# Power_Circuit.net
KiCad netlist of a schematic drawn in Altium Designer
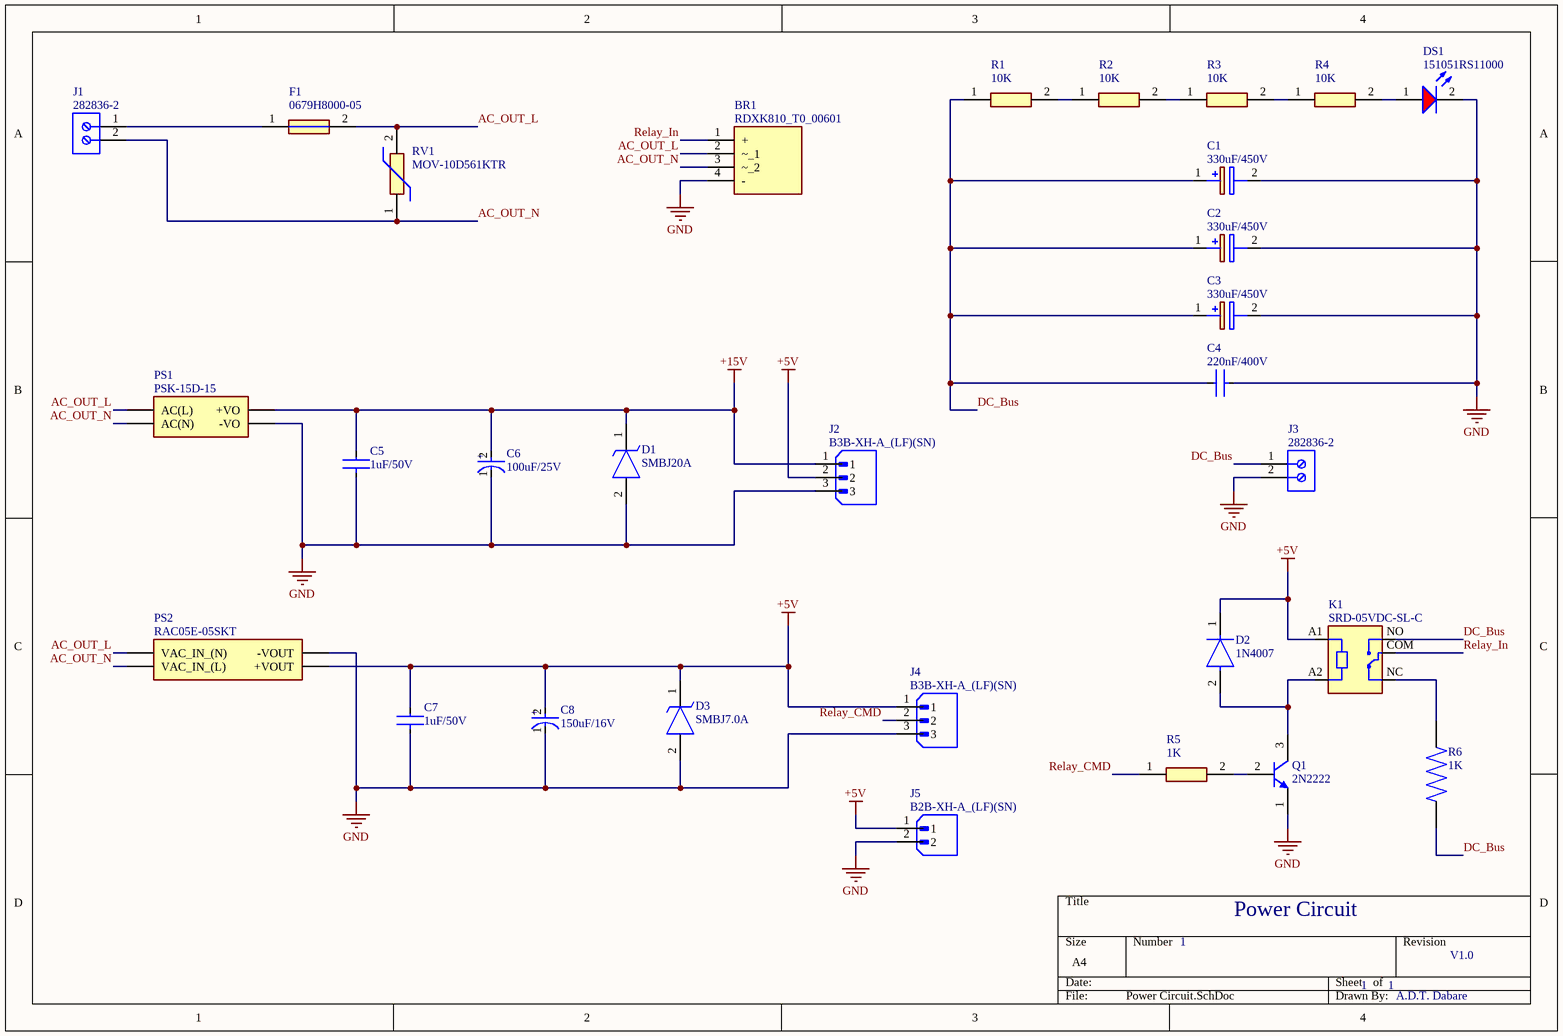
[diagram p0: Power Circuit.SchDoc]

(export (version "E")
  (design (tool "Eeschema 10.0.6"))
  (components
    (comp (ref "BR1")
      (value "RDXK810_T0_00601")
      (footprint "SamacSys:RDXK810_T0_00601")
      (description "Bridge Rectifier")
      (fields (field (name "MOUSER PART NUMBER") "241-RDXK810_T0_00601"))
      (libsource (lib "*") (part "RDXK810_T0_00601"))
    )
    (comp (ref "C1")
      (value "330uF/450V")
      (footprint "SamacSys:CAPPRD1000W190D3050H3200")
      (description "Capacitor Polarised")
      (fields
        (field (name "MANUFACTURER_PART_NUMBER") "B43647B5337M057")
        (field (name "MOUSER PART NUMBER") "871-B43647B5337M057")
      )
      (libsource (lib "*") (part "B43647B5337M057"))
    )
    (comp (ref "C2")
      (value "330uF/450V")
      (footprint "SamacSys:CAPPRD1000W190D3050H3200")
      (description "Capacitor Polarised")
      (fields
        (field (name "MANUFACTURER_PART_NUMBER") "B43647B5337M057")
        (field (name "MOUSER PART NUMBER") "871-B43647B5337M057")
      )
      (libsource (lib "*") (part "B43647B5337M057"))
    )
    (comp (ref "C3")
      (value "330uF/450V")
      (footprint "SamacSys:CAPPRD1000W190D3050H3200")
      (description "Capacitor Polarised")
      (fields
        (field (name "MANUFACTURER_PART_NUMBER") "B43647B5337M057")
        (field (name "MOUSER PART NUMBER") "871-B43647B5337M057")
      )
      (libsource (lib "*") (part "B43647B5337M057"))
    )
    (comp (ref "C4")
      (value "220nF/400V")
      (footprint "FP-CK06BX105K-MFG")
      (description "CAP CER 1UF 50V BX RADIAL")
      (fields (field (name "TOLERANCE") "10%"))
      (libsource (lib "Altium Content Vault") (part "b4654b650e69147ec39a6b967a45e02"))
    )
    (comp (ref "C5")
      (value "1uF/50V")
      (footprint "FP-CK06BX105K-MFG")
      (description "CAP CER 1UF 50V BX RADIAL")
      (fields (field (name "TOLERANCE") "10%"))
      (libsource (lib "Altium Content Vault") (part "b4654b650e69147ec39a6b967a45e02"))
    )
    (comp (ref "C6")
      (value "100uF/25V")
      (footprint "FP-RAD-TH-D_6_3_0_5-L_11-MFG")
      (description "Aluminum Electrolytic Capacitors (Radial Lead Type) AEC-Q200 Qualified 100uF ±20% 25V")
      (fields (field (name "TOLERANCE") "20%"))
      (libsource (lib "Altium Content Vault") (part "203bc49f2ac43e59fd269a8c329ed05"))
    )
    (comp (ref "C7")
      (value "1uF/50V")
      (footprint "FP-CK06BX105K-MFG")
      (description "CAP CER 1UF 50V BX RADIAL")
      (fields (field (name "TOLERANCE") "10%"))
      (libsource (lib "Altium Content Vault") (part "b4654b650e69147ec39a6b967a45e02"))
    )
    (comp (ref "C8")
      (value "150uF/16V")
      (footprint "FP-RAD-TH-D_6_3_0_5-L_11-MFG")
      (description "Aluminum Electrolytic Capacitors (Radial Lead Type) AEC-Q200 Qualified 100uF ±20% 25V")
      (fields (field (name "TOLERANCE") "20%"))
      (libsource (lib "Altium Content Vault") (part "203bc49f2ac43e59fd269a8c329ed05"))
    )
    (comp (ref "D1")
      (value "SMBJ20A")
      (footprint "SamacSys:DIOM5436X244N")
      (description "TVS Diode (Uni-directional)")
      (fields (field (name "MOUSER PART NUMBER") "652-SMBJ20A"))
      (libsource (lib "*") (part "SMBJ20A"))
    )
    (comp (ref "D2")
      (value "1N4007")
      (footprint "FP-1N4007-MFG")
      (description "Rectifier diode 1000 V 1 A DO-41, ,")
      (fields
        (field (name "MANUFACTURER") "Diotec")
        (field (name "OCTOPART") "https://octopart.com/1n4007-diotec-4040411")
      )
      (libsource (lib "Altium Content Vault") (part "d7152d700b627762746794eb795d46e"))
    )
    (comp (ref "D3")
      (value "SMBJ7.0A")
      (footprint "SamacSys:DIOM5443X244N")
      (description "TVS Diode (Uni-directional)")
      (fields (field (name "MOUSER PART NUMBER") "652-SMBJ7.0A"))
      (libsource (lib "*") (part "SMBJ7.0A"))
    )
    (comp (ref "DS1")
      (value "151051RS11000")
      (footprint "WL-TMRC_D5.9H8.7")
      (libsource (lib "Altium Content Vault") (part "LED_Red_1A-2K"))
    )
    (comp (ref "F1")
      (value "0679H8000-05")
      (footprint "SamacSys:FUSC6125X279N")
      (description "Fuse")
      (libsource (lib "*") (part "0679H8000-05"))
    )
    (comp (ref "J1")
      (value "282836-2")
      (footprint "TECO-282836-2_V")
      (description "Female Header, Pitch 5 mm, 1 x 2 Position, Height 10 mm, Tail Length 3.5 mm, Rohs, Bulk")
      (fields (field (name "VOLTAGE") "300V") (field (name "MANUFACTURER") "TE Connectivity"))
      (libsource (lib "Altium Content Vault") (part "CN-1P-F-TB2"))
    )
    (comp (ref "J2")
      (value "B3B-XH-A_(LF)(SN)")
      (footprint "JST_B3B-XH-A (LF)(SN)")
      (description "Connector Header Through Hole 3 position 0.098 (2.50mm)")
      (fields (field (name "MF") "JST Sales America Inc.") (field (name "MP") "B3B-XH-A (LF)(SN)"))
      (libsource (lib "B3B-XH-A__LF__SN_") (part "B3B-XH-A_(LF)(SN)"))
    )
    (comp (ref "J3")
      (value "282836-2")
      (footprint "TECO-282836-2_V")
      (description "Female Header, Pitch 5 mm, 1 x 2 Position, Height 10 mm, Tail Length 3.5 mm, Rohs, Bulk")
      (fields (field (name "VOLTAGE") "300V") (field (name "MANUFACTURER") "TE Connectivity"))
      (libsource (lib "Altium Content Vault") (part "CN-1P-F-TB2"))
    )
    (comp (ref "J4")
      (value "B3B-XH-A_(LF)(SN)")
      (footprint "JST_B3B-XH-A (LF)(SN)")
      (description "Connector Header Through Hole 3 position 0.098 (2.50mm)")
      (fields (field (name "MF") "JST Sales America Inc.") (field (name "MP") "B3B-XH-A (LF)(SN)"))
      (libsource (lib "B3B-XH-A__LF__SN_") (part "B3B-XH-A_(LF)(SN)"))
    )
    (comp (ref "J5")
      (value "B2B-XH-A_(LF)(SN)")
      (footprint "JST_B2B-XH-A_(LF)(SN)")
      (description "Connector Header Through Hole 2 position 0.098 (2.50mm)")
      (fields (field (name "MF") "JST Sales") (field (name "MP") "B2B-XH-A (LF)(SN)"))
      (libsource (lib "B2B-XH-A__LF__SN_") (part "B2B-XH-A_(LF)(SN)"))
    )
    (comp (ref "K1")
      (value "SRD-05VDC-SL-C")
      (footprint "RELAY_SRD-05VDC-SL-C")
      (fields (field (name "MF") "Songle Relay"))
      (libsource (lib "SRD-05VDC-SL-C") (part "SRD-05VDC-SL-C"))
    )
    (comp (ref "PS1")
      (value "PSK-15D-15")
      (footprint "SamacSys:PSK15D15")
      (description "Power Supply")
      (fields (field (name "MOUSER PART NUMBER") "490-PSK-15D-15"))
      (libsource (lib "*") (part "PSK-15D-15"))
    )
    (comp (ref "PS2")
      (value "RAC05E-05SKT")
      (footprint "SamacSys:RAC05E05SKT")
      (description "Power Supply")
      (fields (field (name "MOUSER PART NUMBER") "919-RAC05E-05SKT"))
      (libsource (lib "*") (part "RAC05E-05SKT"))
    )
    (comp (ref "Q1")
      (value "2N2222")
      (footprint "MLTC-TO-18-3")
      (description "Low Power Bipolar NPN Transistor, 30 V, -65 to 200 degC, 3-Pin TO-18, RoHS, Bulk")
      (fields (field (name "MANUFACTURER") "Multicomp"))
      (libsource (lib "Altium Content Vault") (part "BJT-NPN-EBC-3"))
    )
    (comp (ref "R1")
      (value "10K")
      (footprint "SamacSys:RESC6331X80N")
      (description "Resistor")
      (fields
        (field (name "MANUFACTURER_PART_NUMBER") "CRM2512QJW-103ELF")
        (field (name "MOUSER PART NUMBER") "652-CRM2512QJW-103E")
      )
      (libsource (lib "*") (part "CRM2512QJW-103ELF"))
    )
    (comp (ref "R2")
      (value "10K")
      (footprint "SamacSys:RESC6331X80N")
      (description "Resistor")
      (fields
        (field (name "MANUFACTURER_PART_NUMBER") "CRM2512QJW-103ELF")
        (field (name "MOUSER PART NUMBER") "652-CRM2512QJW-103E")
      )
      (libsource (lib "*") (part "CRM2512QJW-103ELF"))
    )
    (comp (ref "R3")
      (value "10K")
      (footprint "SamacSys:RESC6331X80N")
      (description "Resistor")
      (fields
        (field (name "MANUFACTURER_PART_NUMBER") "CRM2512QJW-103ELF")
        (field (name "MOUSER PART NUMBER") "652-CRM2512QJW-103E")
      )
      (libsource (lib "*") (part "CRM2512QJW-103ELF"))
    )
    (comp (ref "R4")
      (value "10K")
      (footprint "SamacSys:RESC6331X80N")
      (description "Resistor")
      (fields
        (field (name "MANUFACTURER_PART_NUMBER") "CRM2512QJW-103ELF")
        (field (name "MOUSER PART NUMBER") "652-CRM2512QJW-103E")
      )
      (libsource (lib "*") (part "CRM2512QJW-103ELF"))
    )
    (comp (ref "R5")
      (value "1K")
      (footprint "SamacSys:RESC3225X70N")
      (description "Resistor")
      (fields
        (field (name "MANUFACTURER_PART_NUMBER") "ERJ-T14LK102U")
        (field (name "MOUSER PART NUMBER") "667-ERJ-T14LK102U")
      )
      (libsource (lib "*") (part "ERJ-T14LK102U"))
    )
    (comp (ref "R6")
      (value "1K")
      (footprint "RESAD2860W80L2200D950")
      (fields (field (name "MF") "{'manufacturer': u'YAGEO'}") (field (name "MP") "SQP500JB-1K"))
      (libsource (lib "SQP500JB-1K") (part "SQP500JB-1K"))
    )
    (comp (ref "RV1")
      (value "MOV-10D561KTR")
      (footprint "SamacSys:MOV10D561KTR")
      (description "Varistor")
      (fields (field (name "MOUSER PART NUMBER") "652-MOV-10D561KTR"))
      (libsource (lib "*") (part "MOV-10D561KTR"))
    )
  )
  (nets
    (net (code "1") (name "+5V") (class "Default")
      (node (ref "C7") (pin "2") (pinfunction "2_2") (pintype "passive"))
      (node (ref "C8") (pin "2") (pinfunction "A_2") (pintype "passive"))
      (node (ref "D2") (pin "1") (pinfunction "C_1") (pintype "passive"))
      (node (ref "D3") (pin "1") (pinfunction "K_1") (pintype "passive"))
      (node (ref "J2") (pin "2") (pinfunction "2_2") (pintype "passive"))
      (node (ref "J4") (pin "1") (pinfunction "1_1") (pintype "passive"))
      (node (ref "J5") (pin "1") (pinfunction "1_1") (pintype "passive"))
      (node (ref "K1") (pin "A1") (pinfunction "A1_A1") (pintype "passive"))
      (node (ref "PS2") (pin "7") (pinfunction "+VOUT_7") (pintype "passive"))
    )
    (net (code "2") (name "+15V") (class "Default")
      (node (ref "C5") (pin "2") (pinfunction "2_2") (pintype "passive"))
      (node (ref "C6") (pin "2") (pinfunction "A_2") (pintype "passive"))
      (node (ref "D1") (pin "1") (pinfunction "K_1") (pintype "passive"))
      (node (ref "J2") (pin "1") (pinfunction "1_1") (pintype "passive"))
      (node (ref "PS1") (pin "4") (pinfunction "+VO_4") (pintype "passive"))
    )
    (net (code "3") (name "/AC_OUT_L") (class "Default")
      (node (ref "BR1") (pin "2") (pinfunction "~_1_2") (pintype "passive"))
      (node (ref "F1") (pin "2") (pinfunction "2_2") (pintype "passive"))
      (node (ref "PS1") (pin "1") (pinfunction "AC(L)_1") (pintype "passive"))
      (node (ref "PS2") (pin "1") (pinfunction "VAC_IN_(N)_1") (pintype "passive"))
      (node (ref "RV1") (pin "2") (pinfunction "2_2") (pintype "passive"))
    )
    (net (code "4") (name "/AC_OUT_N") (class "Default")
      (node (ref "BR1") (pin "3") (pinfunction "~_2_3") (pintype "passive"))
      (node (ref "J1") (pin "2") (pinfunction "2_2") (pintype "passive"))
      (node (ref "PS1") (pin "2") (pinfunction "AC(N)_2") (pintype "passive"))
      (node (ref "PS2") (pin "5") (pinfunction "VAC_IN_(L)_5") (pintype "passive"))
      (node (ref "RV1") (pin "1") (pinfunction "1_1") (pintype "passive"))
    )
    (net (code "5") (name "/DC_Bus") (class "Default")
      (node (ref "C1") (pin "1") (pinfunction "+_1") (pintype "passive"))
      (node (ref "C2") (pin "1") (pinfunction "+_1") (pintype "passive"))
      (node (ref "C3") (pin "1") (pinfunction "+_1") (pintype "passive"))
      (node (ref "C4") (pin "2") (pinfunction "2_2") (pintype "passive"))
      (node (ref "J3") (pin "1") (pinfunction "1_1") (pintype "passive"))
      (node (ref "K1") (pin "NO") (pinfunction "NO_NO") (pintype "passive"))
      (node (ref "R1") (pin "1") (pinfunction "1_1") (pintype "passive"))
      (node (ref "R6") (pin "1") (pinfunction "1_1") (pintype "passive"))
    )
    (net (code "6") (name "/Relay_CMD") (class "Default")
      (node (ref "J4") (pin "2") (pinfunction "2_2") (pintype "passive"))
      (node (ref "R5") (pin "1") (pinfunction "1_1") (pintype "passive"))
    )
    (net (code "7") (name "/Relay_In") (class "Default")
      (node (ref "BR1") (pin "1") (pinfunction "+_1") (pintype "passive"))
      (node (ref "K1") (pin "COM") (pinfunction "COM_COM") (pintype "passive"))
    )
    (net (code "8") (name "GND") (class "Default")
      (node (ref "BR1") (pin "4") (pinfunction "-_4") (pintype "passive"))
      (node (ref "C1") (pin "2") (pinfunction "-_2") (pintype "passive"))
      (node (ref "C2") (pin "2") (pinfunction "-_2") (pintype "passive"))
      (node (ref "C3") (pin "2") (pinfunction "-_2") (pintype "passive"))
      (node (ref "C4") (pin "1") (pinfunction "1_1") (pintype "passive"))
      (node (ref "C5") (pin "1") (pinfunction "1_1") (pintype "passive"))
      (node (ref "C6") (pin "1") (pinfunction "C_1") (pintype "passive"))
      (node (ref "C7") (pin "1") (pinfunction "1_1") (pintype "passive"))
      (node (ref "C8") (pin "1") (pinfunction "C_1") (pintype "passive"))
      (node (ref "D1") (pin "2") (pinfunction "A_2") (pintype "passive"))
      (node (ref "D3") (pin "2") (pinfunction "A_2") (pintype "passive"))
      (node (ref "DS1") (pin "2") (pinfunction "K_2") (pintype "passive"))
      (node (ref "J2") (pin "3") (pinfunction "3_3") (pintype "passive"))
      (node (ref "J3") (pin "2") (pinfunction "2_2") (pintype "passive"))
      (node (ref "J4") (pin "3") (pinfunction "3_3") (pintype "passive"))
      (node (ref "J5") (pin "2") (pinfunction "2_2") (pintype "passive"))
      (node (ref "PS1") (pin "3") (pinfunction "-VO_3") (pintype "passive"))
      (node (ref "PS2") (pin "9") (pinfunction "-VOUT_9") (pintype "passive"))
      (node (ref "Q1") (pin "1") (pinfunction "E_1") (pintype "passive"))
    )
    (net (code "9") (name "Net-(D2-A)") (class "Default")
      (node (ref "D2") (pin "2") (pinfunction "A_2") (pintype "passive"))
      (node (ref "K1") (pin "A2") (pinfunction "A2_A2") (pintype "passive"))
      (node (ref "Q1") (pin "3") (pinfunction "C_3") (pintype "passive"))
    )
    (net (code "10") (name "Net-(DS1-A)") (class "Default")
      (node (ref "DS1") (pin "1") (pinfunction "A_1") (pintype "passive"))
      (node (ref "R4") (pin "2") (pinfunction "2_2") (pintype "passive"))
    )
    (net (code "11") (name "Net-(F1-Pad1)") (class "Default")
      (node (ref "F1") (pin "1") (pinfunction "1_1") (pintype "passive"))
      (node (ref "J1") (pin "1") (pinfunction "1_1") (pintype "passive"))
    )
    (net (code "12") (name "Net-(K1-PadNC)") (class "Default")
      (node (ref "K1") (pin "NC") (pinfunction "NC_NC") (pintype "passive"))
      (node (ref "R6") (pin "2") (pinfunction "2_2") (pintype "passive"))
    )
    (net (code "13") (name "Net-(Q1-B)") (class "Default")
      (node (ref "Q1") (pin "2") (pinfunction "B_2") (pintype "passive"))
      (node (ref "R5") (pin "2") (pinfunction "2_2") (pintype "passive"))
    )
    (net (code "14") (name "Net-(R1-Pad2)") (class "Default")
      (node (ref "R1") (pin "2") (pinfunction "2_2") (pintype "passive"))
      (node (ref "R2") (pin "1") (pinfunction "1_1") (pintype "passive"))
    )
    (net (code "15") (name "Net-(R2-Pad2)") (class "Default")
      (node (ref "R2") (pin "2") (pinfunction "2_2") (pintype "passive"))
      (node (ref "R3") (pin "1") (pinfunction "1_1") (pintype "passive"))
    )
    (net (code "16") (name "Net-(R3-Pad2)") (class "Default")
      (node (ref "R3") (pin "2") (pinfunction "2_2") (pintype "passive"))
      (node (ref "R4") (pin "1") (pinfunction "1_1") (pintype "passive"))
    )
  )
)
